# ResetCircuit.net
KiCad netlist of a schematic drawn in Altium Designer
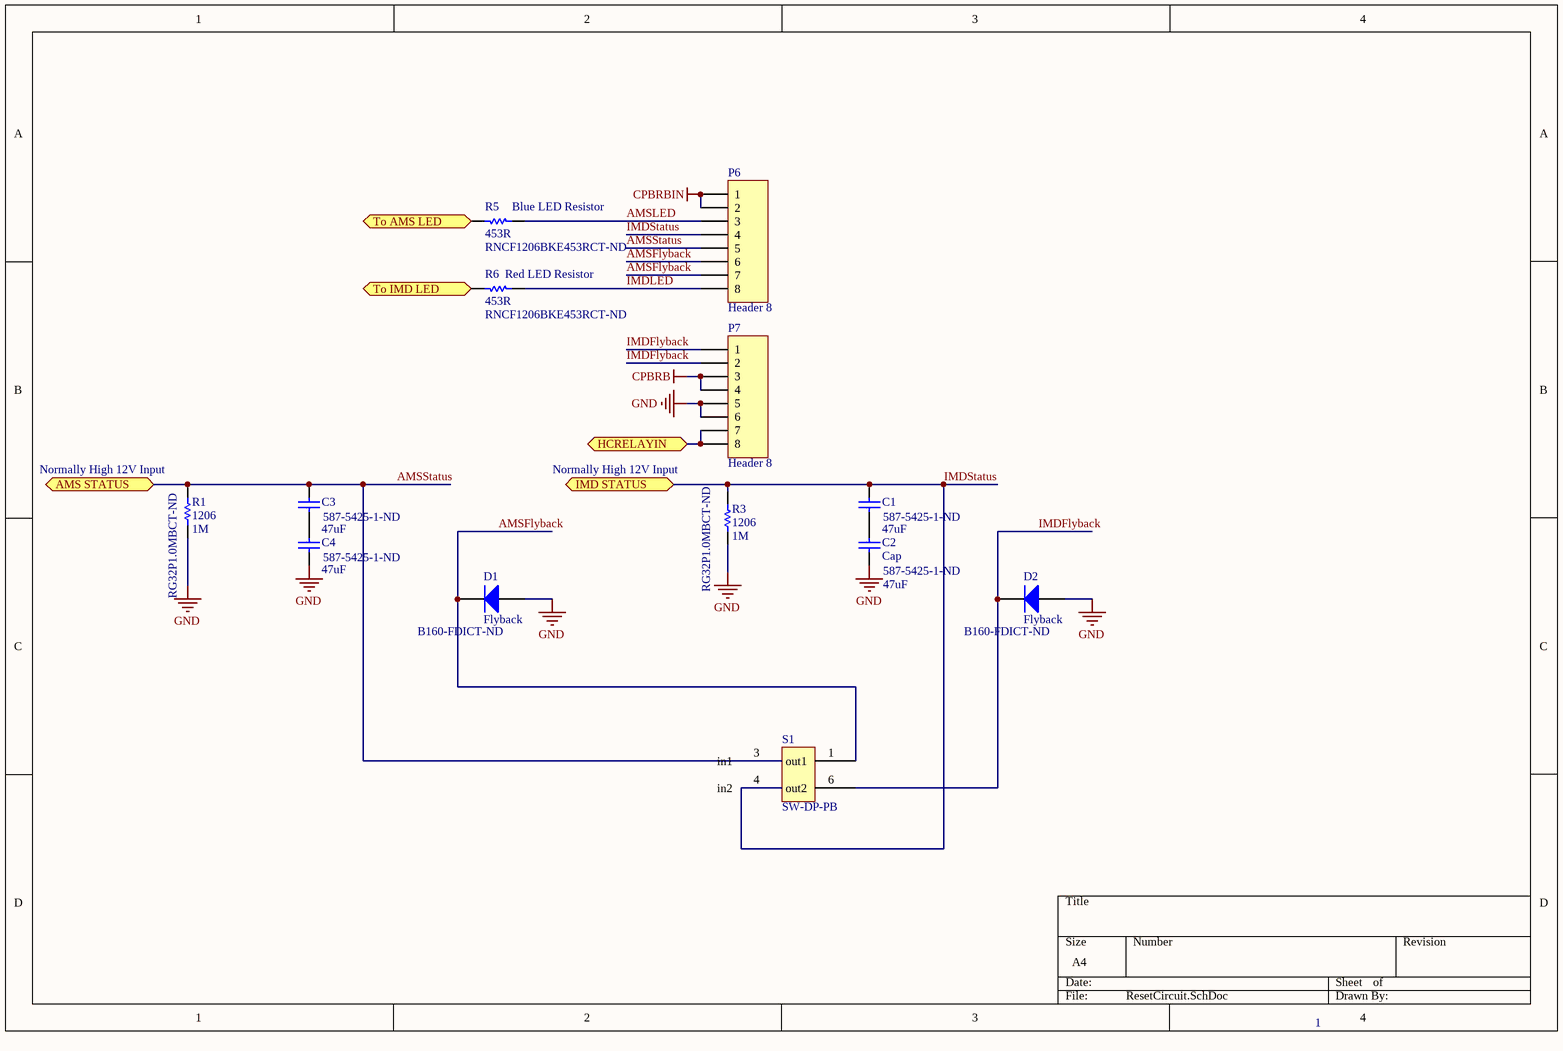
[diagram p0: ResetCircuit.SchDoc]

(export (version "E")
  (design (tool "Eeschema 10.0.6"))
  (components
    (comp (ref "C1")
      (value "47uF")
      (footprint "C1206")
      (description "Capacitor")
      (fields
        (field (name "SUPPLIER PART NUMBER 1") "587-5425-1-ND")
        (field (name "Comment") "Cap")
        (field (name "PUBLISHER") "Altium Limited")
      )
      (libsource (lib "Miscellaneous Devices") (part "Cap"))
    )
    (comp (ref "C2")
      (value "Cap")
      (footprint "C1206")
      (description "Capacitor")
      (fields
        (field (name "ALTIUM_VALUE") "47uF")
        (field (name "SUPPLIER PART NUMBER 1") "587-5425-1-ND")
        (field (name "PUBLISHER") "Altium Limited")
      )
      (libsource (lib "Miscellaneous Devices") (part "Cap"))
    )
    (comp (ref "C3")
      (value "47uF")
      (footprint "C1206")
      (description "Capacitor")
      (fields
        (field (name "SUPPLIER PART NUMBER 1") "587-5425-1-ND")
        (field (name "Comment") "Cap")
        (field (name "PUBLISHER") "Altium Limited")
      )
      (libsource (lib "Miscellaneous Devices") (part "Cap"))
    )
    (comp (ref "C4")
      (value "47uF")
      (footprint "C1206")
      (description "Capacitor")
      (fields
        (field (name "SUPPLIER PART NUMBER 1") "587-5425-1-ND")
        (field (name "Comment") "Cap")
        (field (name "PUBLISHER") "Altium Limited")
      )
      (libsource (lib "Miscellaneous Devices") (part "Cap"))
    )
    (comp (ref "D1")
      (value "Flyback")
      (footprint "DO-214AC, SMA")
      (description "Default Diode")
      (fields
        (field (name "SUPPLIER PART NUMBER 1") "B160-FDICT-ND")
        (field (name "PUBLISHER") "Altium Limited")
      )
      (libsource (lib "Miscellaneous Devices") (part "Diode"))
    )
    (comp (ref "D2")
      (value "Flyback")
      (footprint "DO-214AC, SMA")
      (description "Default Diode")
      (fields
        (field (name "SUPPLIER PART NUMBER 1") "B160-FDICT-ND")
        (field (name "PUBLISHER") "Altium Limited")
      )
      (libsource (lib "Miscellaneous Devices") (part "Diode"))
    )
    (comp (ref "P6")
      (value "Header 8")
      (footprint "HDR1X8")
      (description "Header, 8-Pin, A98338-ND")
      (fields (field (name "PUBLISHER") "Altium Limited"))
      (libsource (lib "Miscellaneous Connectors") (part "Header 8"))
    )
    (comp (ref "P7")
      (value "Header 8")
      (footprint "HDR1X8")
      (description "Header, 8-Pin A98338-ND")
      (fields (field (name "PUBLISHER") "Altium Limited"))
      (libsource (lib "Miscellaneous Connectors") (part "Header 8"))
    )
    (comp (ref "R1")
      (value "1206")
      (footprint "1206 (High Density)")
      (description "Resistor")
      (fields
        (field (name "ALTIUM_VALUE") "1M")
        (field (name "SUPPLIER PART NUMBER 1") "RG32P1.0MBCT-ND")
        (field (name "PUBLISHER") "Altium Limited")
      )
      (libsource (lib "Miscellaneous Devices") (part "Res1"))
    )
    (comp (ref "R3")
      (value "1206")
      (footprint "1206 (High Density)")
      (description "Resistor")
      (fields
        (field (name "ALTIUM_VALUE") "1M")
        (field (name "SUPPLIER PART NUMBER 1") "RG32P1.0MBCT-ND")
        (field (name "PUBLISHER") "Altium Limited")
      )
      (libsource (lib "Miscellaneous Devices") (part "Res1"))
    )
    (comp (ref "R5")
      (value "Blue LED Resistor")
      (footprint "C1206")
      (description "Resistor")
      (fields
        (field (name "ALTIUM_VALUE") "453R")
        (field (name "SUPPLIER PART NUMBER 1") "RNCF1206BKE453RCT-ND")
        (field (name "PUBLISHER") "Altium Limited")
      )
      (libsource (lib "Miscellaneous Devices") (part "Res1"))
    )
    (comp (ref "R6")
      (value "Red LED Resistor")
      (footprint "C1206")
      (description "Resistor")
      (fields
        (field (name "ALTIUM_VALUE") "453R")
        (field (name "SUPPLIER PART NUMBER 1") "RNCF1206BKE453RCT-ND")
        (field (name "PUBLISHER") "Altium Limited")
      )
      (libsource (lib "Miscellaneous Devices") (part "Res1"))
    )
    (comp (ref "S1")
      (value "SW-DP-PB")
      (footprint "SW-DP-PB")
      (libsource (lib "UVICHybridLibrary") (part "SW-DP-PB"))
    )
  )
  (nets
    (net (code "1") (name "/AMSFlyback") (class "Default")
      (node (ref "D1") (pin "2") (pinfunction "K_2") (pintype "passive"))
      (node (ref "P6") (pin "6") (pinfunction "6_6") (pintype "passive"))
      (node (ref "P6") (pin "7") (pinfunction "7_7") (pintype "passive"))
      (node (ref "S1") (pin "1") (pinfunction "out1_1") (pintype "passive"))
    )
    (net (code "2") (name "/AMSLED") (class "Default")
      (node (ref "P6") (pin "3") (pinfunction "3_3") (pintype "passive"))
      (node (ref "R5") (pin "2") (pinfunction "2_2") (pintype "passive"))
    )
    (net (code "3") (name "/AMSStatus") (class "Default")
      (node (ref "C3") (pin "2") (pinfunction "2_2") (pintype "passive"))
      (node (ref "P6") (pin "5") (pinfunction "5_5") (pintype "passive"))
      (node (ref "R1") (pin "2") (pinfunction "2_2") (pintype "passive"))
      (node (ref "S1") (pin "3") (pinfunction "in1_3") (pintype "passive"))
    )
    (net (code "4") (name "/HCRELAYIN") (class "Default")
      (node (ref "P7") (pin "7") (pinfunction "7_7") (pintype "passive"))
      (node (ref "P7") (pin "8") (pinfunction "8_8") (pintype "passive"))
    )
    (net (code "5") (name "/IMDFlyback") (class "Default")
      (node (ref "D2") (pin "2") (pinfunction "K_2") (pintype "passive"))
      (node (ref "P7") (pin "1") (pinfunction "1_1") (pintype "passive"))
      (node (ref "P7") (pin "2") (pinfunction "2_2") (pintype "passive"))
      (node (ref "S1") (pin "6") (pinfunction "out2_6") (pintype "passive"))
    )
    (net (code "6") (name "/IMDLED") (class "Default")
      (node (ref "P6") (pin "8") (pinfunction "8_8") (pintype "passive"))
      (node (ref "R6") (pin "2") (pinfunction "2_2") (pintype "passive"))
    )
    (net (code "7") (name "/IMDStatus") (class "Default")
      (node (ref "C1") (pin "2") (pinfunction "2_2") (pintype "passive"))
      (node (ref "P6") (pin "4") (pinfunction "4_4") (pintype "passive"))
      (node (ref "R3") (pin "2") (pinfunction "2_2") (pintype "passive"))
      (node (ref "S1") (pin "4") (pinfunction "in2_4") (pintype "passive"))
    )
    (net (code "8") (name "/To AMS LED") (class "Default")
      (node (ref "R5") (pin "1") (pinfunction "1_1") (pintype "passive"))
    )
    (net (code "9") (name "/To IMD LED") (class "Default")
      (node (ref "R6") (pin "1") (pinfunction "1_1") (pintype "passive"))
    )
    (net (code "10") (name "CPBRB") (class "Default")
      (node (ref "P7") (pin "3") (pinfunction "3_3") (pintype "passive"))
      (node (ref "P7") (pin "4") (pinfunction "4_4") (pintype "passive"))
    )
    (net (code "11") (name "CPBRBIN") (class "Default")
      (node (ref "P6") (pin "1") (pinfunction "1_1") (pintype "passive"))
      (node (ref "P6") (pin "2") (pinfunction "2_2") (pintype "passive"))
    )
    (net (code "12") (name "GND") (class "Default")
      (node (ref "C2") (pin "1") (pinfunction "1_1") (pintype "passive"))
      (node (ref "C4") (pin "1") (pinfunction "1_1") (pintype "passive"))
      (node (ref "D1") (pin "1") (pinfunction "A_1") (pintype "passive"))
      (node (ref "D2") (pin "1") (pinfunction "A_1") (pintype "passive"))
      (node (ref "P7") (pin "5") (pinfunction "5_5") (pintype "passive"))
      (node (ref "P7") (pin "6") (pinfunction "6_6") (pintype "passive"))
      (node (ref "R1") (pin "1") (pinfunction "1_1") (pintype "passive"))
      (node (ref "R3") (pin "1") (pinfunction "1_1") (pintype "passive"))
    )
    (net (code "13") (name "Net-(C1-Pad1)") (class "Default")
      (node (ref "C1") (pin "1") (pinfunction "1_1") (pintype "passive"))
      (node (ref "C2") (pin "2") (pinfunction "2_2") (pintype "passive"))
    )
    (net (code "14") (name "Net-(C3-Pad1)") (class "Default")
      (node (ref "C3") (pin "1") (pinfunction "1_1") (pintype "passive"))
      (node (ref "C4") (pin "2") (pinfunction "2_2") (pintype "passive"))
    )
  )
)
